# QCopterFC_KEY_Sch.net
KiCad netlist of a schematic drawn in Altium Designer
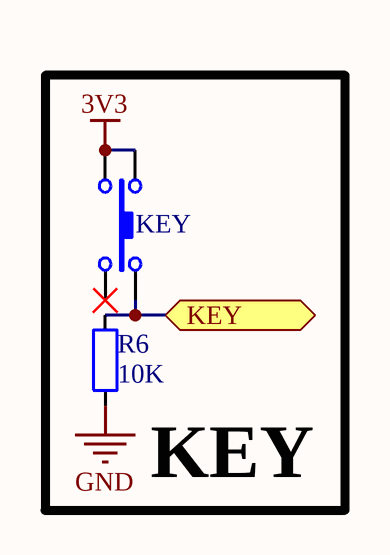
[diagram p0: QCopterFC_KEY_Sch.SchDoc]

(export (version "E")
  (design (tool "Eeschema 10.0.6"))
  (components
    (comp (ref "KEY")
      (value "BT_TACT_3.5*5_90")
      (footprint "PCB_Switch:BT_TACT_3.5*3.55_90")
      (description "Switch")
      (libsource (lib "SCH_Switch") (part "BT_TACT_3.5*5_90"))
    )
    (comp (ref "R6")
      (value "10K")
      (footprint "PCB_Passive:RES_0603")
      (description "Resistor")
      (fields (field (name "Comment") "Res_0603"))
      (libsource (lib "SCH_Passive") (part "Res_0603"))
    )
  )
  (nets
    (net (code "1") (name "/KEY") (class "Default")
      (node (ref "KEY") (pin "2") (pinfunction "2_2") (pintype "passive"))
      (node (ref "R6") (pin "2") (pinfunction "2_2") (pintype "passive"))
    )
    (net (code "2") (name "3V3") (class "Default")
      (node (ref "KEY") (pin "1") (pinfunction "1_1") (pintype "passive"))
      (node (ref "KEY") (pin "3") (pinfunction "3_3") (pintype "passive"))
    )
    (net (code "3") (name "GND") (class "Default")
      (node (ref "R6") (pin "1") (pinfunction "1_1") (pintype "passive"))
    )
    (net (code "4") (name "unconnected-(KEY-Pad4)") (class "Default")
      (node (ref "KEY") (pin "4") (pinfunction "4_4") (pintype "passive+no_connect"))
    )
  )
)
